# TEC_DRV.net
KiCad netlist of a schematic drawn in Altium Designer
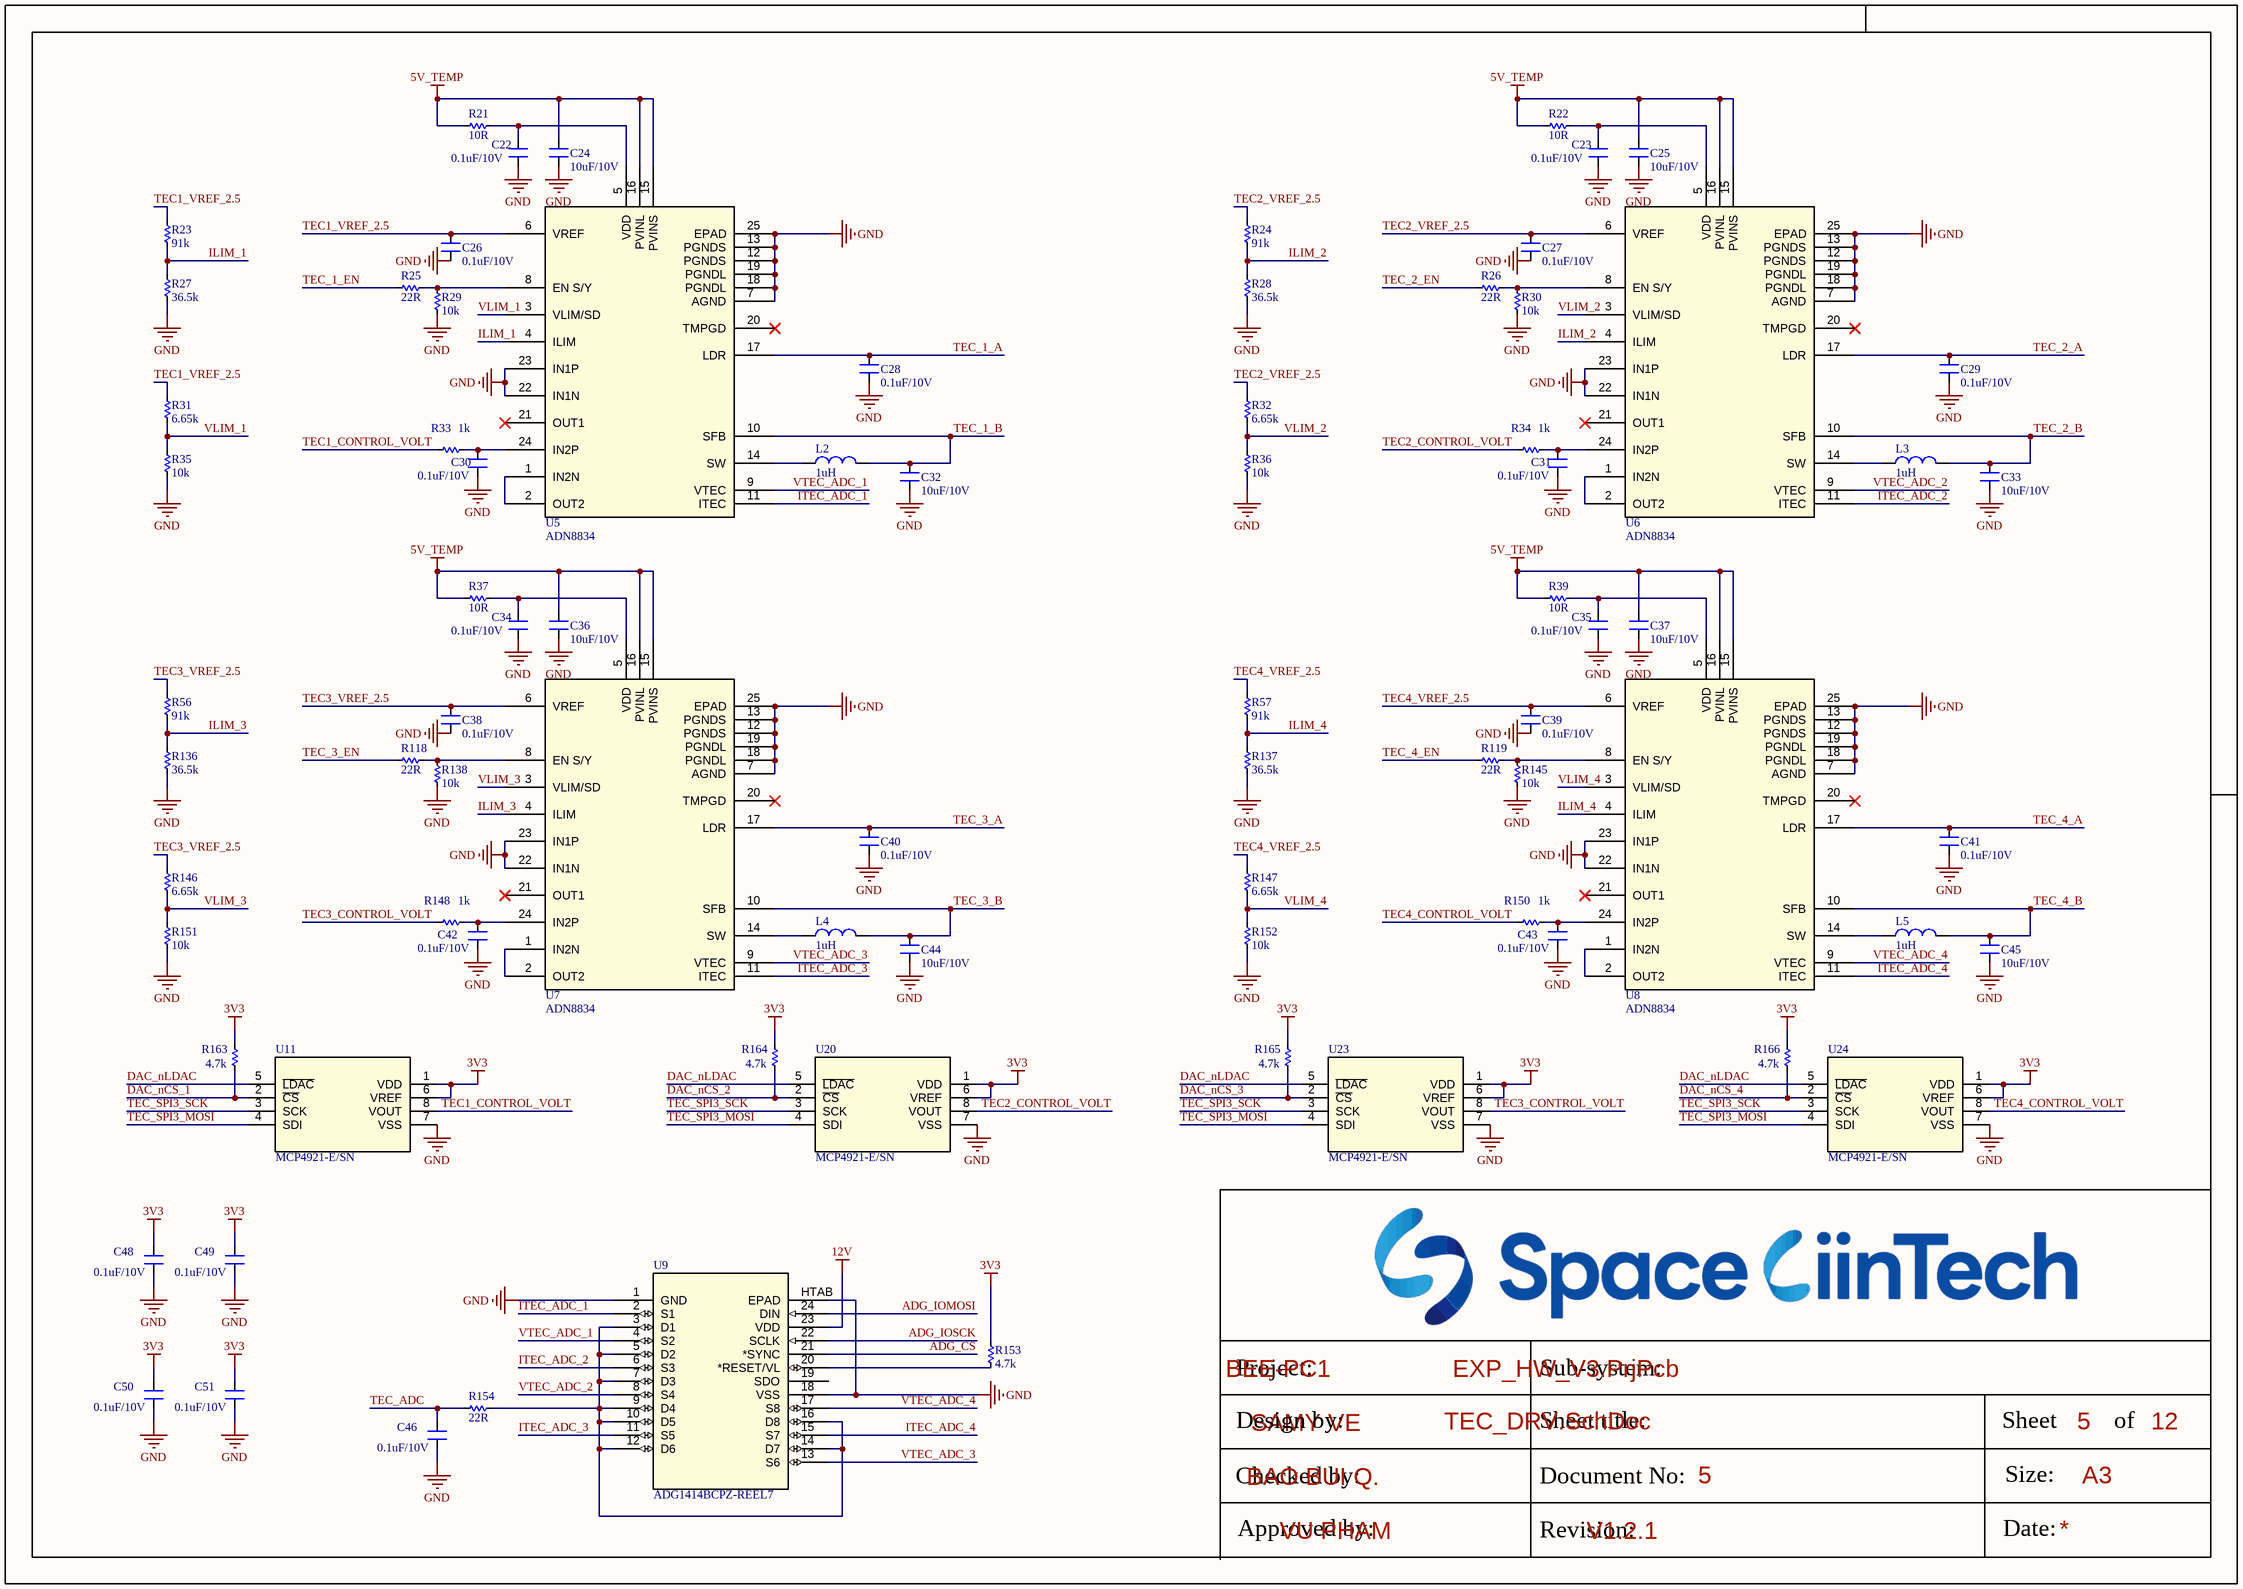
[diagram p0: TEC_DRV.SchDoc]

(export (version "E")
  (design (tool "Eeschema 10.0.6"))
  (components
    (comp (ref "C22")
      (value "0.1uF/10V")
      (footprint "CAP_C_1608X80")
      (libsource (lib "EXP_HW_V3") (part "Capacitors"))
    )
    (comp (ref "C23")
      (value "0.1uF/10V")
      (footprint "CAP_C_1608X80")
      (libsource (lib "EXP_HW_V3") (part "Capacitors"))
    )
    (comp (ref "C24")
      (value "10uF/10V")
      (footprint "CAP_C_1608X80")
      (libsource (lib "EXP_HW_V3") (part "Capacitors"))
    )
    (comp (ref "C25")
      (value "10uF/10V")
      (footprint "CAP_C_1608X80")
      (libsource (lib "EXP_HW_V3") (part "Capacitors"))
    )
    (comp (ref "C26")
      (value "0.1uF/10V")
      (footprint "CAP_C_1608X80")
      (libsource (lib "EXP_HW_V3") (part "Capacitors"))
    )
    (comp (ref "C27")
      (value "0.1uF/10V")
      (footprint "CAP_C_1608X80")
      (libsource (lib "EXP_HW_V3") (part "Capacitors"))
    )
    (comp (ref "C28")
      (value "0.1uF/10V")
      (footprint "CAP_C_1608X80")
      (libsource (lib "EXP_HW_V3") (part "Capacitors"))
    )
    (comp (ref "C29")
      (value "0.1uF/10V")
      (footprint "CAP_C_1608X80")
      (libsource (lib "EXP_HW_V3") (part "Capacitors"))
    )
    (comp (ref "C30")
      (value "0.1uF/10V")
      (footprint "CAP_C_1608X80")
      (libsource (lib "EXP_HW_V3") (part "Capacitors"))
    )
    (comp (ref "C31")
      (value "0.1uF/10V")
      (footprint "CAP_C_1608X80")
      (libsource (lib "EXP_HW_V3") (part "Capacitors"))
    )
    (comp (ref "C32")
      (value "10uF/10V")
      (footprint "CAP_C_1608X80")
      (libsource (lib "EXP_HW_V3") (part "Capacitors"))
    )
    (comp (ref "C33")
      (value "10uF/10V")
      (footprint "CAP_C_1608X80")
      (libsource (lib "EXP_HW_V3") (part "Capacitors"))
    )
    (comp (ref "C34")
      (value "0.1uF/10V")
      (footprint "CAP_C_1608X80")
      (libsource (lib "EXP_HW_V3") (part "Capacitors"))
    )
    (comp (ref "C35")
      (value "0.1uF/10V")
      (footprint "CAP_C_1608X80")
      (libsource (lib "EXP_HW_V3") (part "Capacitors"))
    )
    (comp (ref "C36")
      (value "10uF/10V")
      (footprint "CAP_C_1608X80")
      (libsource (lib "EXP_HW_V3") (part "Capacitors"))
    )
    (comp (ref "C37")
      (value "10uF/10V")
      (footprint "CAP_C_1608X80")
      (libsource (lib "EXP_HW_V3") (part "Capacitors"))
    )
    (comp (ref "C38")
      (value "0.1uF/10V")
      (footprint "CAP_C_1608X80")
      (libsource (lib "EXP_HW_V3") (part "Capacitors"))
    )
    (comp (ref "C39")
      (value "0.1uF/10V")
      (footprint "CAP_C_1608X80")
      (libsource (lib "EXP_HW_V3") (part "Capacitors"))
    )
    (comp (ref "C40")
      (value "0.1uF/10V")
      (footprint "CAP_C_1608X80")
      (libsource (lib "EXP_HW_V3") (part "Capacitors"))
    )
    (comp (ref "C41")
      (value "0.1uF/10V")
      (footprint "CAP_C_1608X80")
      (libsource (lib "EXP_HW_V3") (part "Capacitors"))
    )
    (comp (ref "C42")
      (value "0.1uF/10V")
      (footprint "CAP_C_1608X80")
      (libsource (lib "EXP_HW_V3") (part "Capacitors"))
    )
    (comp (ref "C43")
      (value "0.1uF/10V")
      (footprint "CAP_C_1608X80")
      (libsource (lib "EXP_HW_V3") (part "Capacitors"))
    )
    (comp (ref "C44")
      (value "10uF/10V")
      (footprint "CAP_C_1608X80")
      (libsource (lib "EXP_HW_V3") (part "Capacitors"))
    )
    (comp (ref "C45")
      (value "10uF/10V")
      (footprint "CAP_C_1608X80")
      (libsource (lib "EXP_HW_V3") (part "Capacitors"))
    )
    (comp (ref "C46")
      (value "0.1uF/10V")
      (footprint "CAP_C_1608X80")
      (libsource (lib "EXP_HW_V3") (part "Capacitors"))
    )
    (comp (ref "C48")
      (value "0.1uF/10V")
      (footprint "CAP_C_1608X80")
      (libsource (lib "EXP_HW_V3") (part "Capacitors"))
    )
    (comp (ref "C49")
      (value "0.1uF/10V")
      (footprint "CAP_C_1608X80")
      (libsource (lib "EXP_HW_V3") (part "Capacitors"))
    )
    (comp (ref "C50")
      (value "0.1uF/10V")
      (footprint "CAP_C_1608X80")
      (libsource (lib "EXP_HW_V3") (part "Capacitors"))
    )
    (comp (ref "C51")
      (value "0.1uF/10V")
      (footprint "CAP_C_1608X80")
      (libsource (lib "EXP_HW_V3") (part "Capacitors"))
    )
    (comp (ref "L2")
      (value "1uH")
      (footprint "L-SMD-M-3.5x3.5x2mm")
      (fields
        (field (name "PARTNO") "78477010")
        (field (name "MANUFACTURER") "Wurth Elektronik")
        (field (name "CREATED BY") "Baojun Chen")
      )
      (libsource (lib "EXP_HW_V3") (part "L-SMD-1"))
    )
    (comp (ref "L3")
      (value "1uH")
      (footprint "L-SMD-M-3.5x3.5x2mm")
      (fields
        (field (name "PARTNO") "78477010")
        (field (name "MANUFACTURER") "Wurth Elektronik")
        (field (name "CREATED BY") "Baojun Chen")
      )
      (libsource (lib "EXP_HW_V3") (part "L-SMD-1"))
    )
    (comp (ref "L4")
      (value "1uH")
      (footprint "L-SMD-M-3.5x3.5x2mm")
      (fields
        (field (name "PARTNO") "78477010")
        (field (name "MANUFACTURER") "Wurth Elektronik")
        (field (name "CREATED BY") "Baojun Chen")
      )
      (libsource (lib "EXP_HW_V3") (part "L-SMD-1"))
    )
    (comp (ref "L5")
      (value "1uH")
      (footprint "L-SMD-M-3.5x3.5x2mm")
      (fields
        (field (name "PARTNO") "78477010")
        (field (name "MANUFACTURER") "Wurth Elektronik")
        (field (name "CREATED BY") "Baojun Chen")
      )
      (libsource (lib "EXP_HW_V3") (part "L-SMD-1"))
    )
    (comp (ref "R21")
      (value "10R")
      (footprint "RES_C_1608X60")
      (description "SMD")
      (fields
        (field (name "MANUFACTURER") "Generic Components")
        (field (name "PUBLISHER") "Altium Hobart Technology Centre")
      )
      (libsource (lib "EXP_HW_V3") (part "Res SMD"))
    )
    (comp (ref "R22")
      (value "10R")
      (footprint "RES_C_1608X60")
      (description "SMD")
      (fields
        (field (name "MANUFACTURER") "Generic Components")
        (field (name "PUBLISHER") "Altium Hobart Technology Centre")
      )
      (libsource (lib "EXP_HW_V3") (part "Res SMD"))
    )
    (comp (ref "R23")
      (value "91k")
      (footprint "RES_C_1608X60")
      (description "SMD")
      (fields
        (field (name "MANUFACTURER") "Generic Components")
        (field (name "PUBLISHER") "Altium Hobart Technology Centre")
      )
      (libsource (lib "EXP_HW_V3") (part "Res SMD"))
    )
    (comp (ref "R24")
      (value "91k")
      (footprint "RES_C_1608X60")
      (description "SMD")
      (fields
        (field (name "MANUFACTURER") "Generic Components")
        (field (name "PUBLISHER") "Altium Hobart Technology Centre")
      )
      (libsource (lib "EXP_HW_V3") (part "Res SMD"))
    )
    (comp (ref "R25")
      (value "22R")
      (footprint "RES_C_1608X60")
      (description "SMD")
      (fields
        (field (name "MANUFACTURER") "Generic Components")
        (field (name "PUBLISHER") "Altium Hobart Technology Centre")
      )
      (libsource (lib "EXP_HW_V3") (part "Res SMD"))
    )
    (comp (ref "R26")
      (value "22R")
      (footprint "RES_C_1608X60")
      (description "SMD")
      (fields
        (field (name "MANUFACTURER") "Generic Components")
        (field (name "PUBLISHER") "Altium Hobart Technology Centre")
      )
      (libsource (lib "EXP_HW_V3") (part "Res SMD"))
    )
    (comp (ref "R27")
      (value "36.5k")
      (footprint "RES_C_1608X60")
      (description "SMD")
      (fields
        (field (name "MANUFACTURER") "Generic Components")
        (field (name "PUBLISHER") "Altium Hobart Technology Centre")
      )
      (libsource (lib "EXP_HW_V3") (part "Res SMD"))
    )
    (comp (ref "R28")
      (value "36.5k")
      (footprint "RES_C_1608X60")
      (description "SMD")
      (fields
        (field (name "MANUFACTURER") "Generic Components")
        (field (name "PUBLISHER") "Altium Hobart Technology Centre")
      )
      (libsource (lib "EXP_HW_V3") (part "Res SMD"))
    )
    (comp (ref "R29")
      (value "10k")
      (footprint "RES_C_1608X60")
      (description "SMD")
      (fields
        (field (name "MANUFACTURER") "Generic Components")
        (field (name "PUBLISHER") "Altium Hobart Technology Centre")
      )
      (libsource (lib "EXP_HW_V3") (part "Res SMD"))
    )
    (comp (ref "R30")
      (value "10k")
      (footprint "RES_C_1608X60")
      (description "SMD")
      (fields
        (field (name "MANUFACTURER") "Generic Components")
        (field (name "PUBLISHER") "Altium Hobart Technology Centre")
      )
      (libsource (lib "EXP_HW_V3") (part "Res SMD"))
    )
    (comp (ref "R31")
      (value "6.65k")
      (footprint "RES_C_1608X60")
      (description "SMD")
      (fields
        (field (name "MANUFACTURER") "Generic Components")
        (field (name "PUBLISHER") "Altium Hobart Technology Centre")
      )
      (libsource (lib "EXP_HW_V3") (part "Res SMD"))
    )
    (comp (ref "R32")
      (value "6.65k")
      (footprint "RES_C_1608X60")
      (description "SMD")
      (fields
        (field (name "MANUFACTURER") "Generic Components")
        (field (name "PUBLISHER") "Altium Hobart Technology Centre")
      )
      (libsource (lib "EXP_HW_V3") (part "Res SMD"))
    )
    (comp (ref "R33")
      (value "1k")
      (footprint "RES_C_1608X60")
      (description "SMD")
      (fields
        (field (name "MANUFACTURER") "Generic Components")
        (field (name "PUBLISHER") "Altium Hobart Technology Centre")
      )
      (libsource (lib "EXP_HW_V3") (part "Res SMD"))
    )
    (comp (ref "R34")
      (value "1k")
      (footprint "RES_C_1608X60")
      (description "SMD")
      (fields
        (field (name "MANUFACTURER") "Generic Components")
        (field (name "PUBLISHER") "Altium Hobart Technology Centre")
      )
      (libsource (lib "EXP_HW_V3") (part "Res SMD"))
    )
    (comp (ref "R35")
      (value "10k")
      (footprint "RES_C_1608X60")
      (description "SMD")
      (fields
        (field (name "MANUFACTURER") "Generic Components")
        (field (name "PUBLISHER") "Altium Hobart Technology Centre")
      )
      (libsource (lib "EXP_HW_V3") (part "Res SMD"))
    )
    (comp (ref "R36")
      (value "10k")
      (footprint "RES_C_1608X60")
      (description "SMD")
      (fields
        (field (name "MANUFACTURER") "Generic Components")
        (field (name "PUBLISHER") "Altium Hobart Technology Centre")
      )
      (libsource (lib "EXP_HW_V3") (part "Res SMD"))
    )
    (comp (ref "R37")
      (value "10R")
      (footprint "RES_C_1608X60")
      (description "SMD")
      (fields
        (field (name "MANUFACTURER") "Generic Components")
        (field (name "PUBLISHER") "Altium Hobart Technology Centre")
      )
      (libsource (lib "EXP_HW_V3") (part "Res SMD"))
    )
    (comp (ref "R39")
      (value "10R")
      (footprint "RES_C_1608X60")
      (description "SMD")
      (fields
        (field (name "MANUFACTURER") "Generic Components")
        (field (name "PUBLISHER") "Altium Hobart Technology Centre")
      )
      (libsource (lib "EXP_HW_V3") (part "Res SMD"))
    )
    (comp (ref "R56")
      (value "91k")
      (footprint "RES_C_1608X60")
      (description "SMD")
      (fields
        (field (name "MANUFACTURER") "Generic Components")
        (field (name "PUBLISHER") "Altium Hobart Technology Centre")
      )
      (libsource (lib "EXP_HW_V3") (part "Res SMD"))
    )
    (comp (ref "R57")
      (value "91k")
      (footprint "RES_C_1608X60")
      (description "SMD")
      (fields
        (field (name "MANUFACTURER") "Generic Components")
        (field (name "PUBLISHER") "Altium Hobart Technology Centre")
      )
      (libsource (lib "EXP_HW_V3") (part "Res SMD"))
    )
    (comp (ref "R118")
      (value "22R")
      (footprint "RES_C_1608X60")
      (description "SMD")
      (fields
        (field (name "MANUFACTURER") "Generic Components")
        (field (name "PUBLISHER") "Altium Hobart Technology Centre")
      )
      (libsource (lib "EXP_HW_V3") (part "Res SMD"))
    )
    (comp (ref "R119")
      (value "22R")
      (footprint "RES_C_1608X60")
      (description "SMD")
      (fields
        (field (name "MANUFACTURER") "Generic Components")
        (field (name "PUBLISHER") "Altium Hobart Technology Centre")
      )
      (libsource (lib "EXP_HW_V3") (part "Res SMD"))
    )
    (comp (ref "R136")
      (value "36.5k")
      (footprint "RES_C_1608X60")
      (description "SMD")
      (fields
        (field (name "MANUFACTURER") "Generic Components")
        (field (name "PUBLISHER") "Altium Hobart Technology Centre")
      )
      (libsource (lib "EXP_HW_V3") (part "Res SMD"))
    )
    (comp (ref "R137")
      (value "36.5k")
      (footprint "RES_C_1608X60")
      (description "SMD")
      (fields
        (field (name "MANUFACTURER") "Generic Components")
        (field (name "PUBLISHER") "Altium Hobart Technology Centre")
      )
      (libsource (lib "EXP_HW_V3") (part "Res SMD"))
    )
    (comp (ref "R138")
      (value "10k")
      (footprint "RES_C_1608X60")
      (description "SMD")
      (fields
        (field (name "MANUFACTURER") "Generic Components")
        (field (name "PUBLISHER") "Altium Hobart Technology Centre")
      )
      (libsource (lib "EXP_HW_V3") (part "Res SMD"))
    )
    (comp (ref "R145")
      (value "10k")
      (footprint "RES_C_1608X60")
      (description "SMD")
      (fields
        (field (name "MANUFACTURER") "Generic Components")
        (field (name "PUBLISHER") "Altium Hobart Technology Centre")
      )
      (libsource (lib "EXP_HW_V3") (part "Res SMD"))
    )
    (comp (ref "R146")
      (value "6.65k")
      (footprint "RES_C_1608X60")
      (description "SMD")
      (fields
        (field (name "MANUFACTURER") "Generic Components")
        (field (name "PUBLISHER") "Altium Hobart Technology Centre")
      )
      (libsource (lib "EXP_HW_V3") (part "Res SMD"))
    )
    (comp (ref "R147")
      (value "6.65k")
      (footprint "RES_C_1608X60")
      (description "SMD")
      (fields
        (field (name "MANUFACTURER") "Generic Components")
        (field (name "PUBLISHER") "Altium Hobart Technology Centre")
      )
      (libsource (lib "EXP_HW_V3") (part "Res SMD"))
    )
    (comp (ref "R148")
      (value "1k")
      (footprint "RES_C_1608X60")
      (description "SMD")
      (fields
        (field (name "MANUFACTURER") "Generic Components")
        (field (name "PUBLISHER") "Altium Hobart Technology Centre")
      )
      (libsource (lib "EXP_HW_V3") (part "Res SMD"))
    )
    (comp (ref "R150")
      (value "1k")
      (footprint "RES_C_1608X60")
      (description "SMD")
      (fields
        (field (name "MANUFACTURER") "Generic Components")
        (field (name "PUBLISHER") "Altium Hobart Technology Centre")
      )
      (libsource (lib "EXP_HW_V3") (part "Res SMD"))
    )
    (comp (ref "R151")
      (value "10k")
      (footprint "RES_C_1608X60")
      (description "SMD")
      (fields
        (field (name "MANUFACTURER") "Generic Components")
        (field (name "PUBLISHER") "Altium Hobart Technology Centre")
      )
      (libsource (lib "EXP_HW_V3") (part "Res SMD"))
    )
    (comp (ref "R152")
      (value "10k")
      (footprint "RES_C_1608X60")
      (description "SMD")
      (fields
        (field (name "MANUFACTURER") "Generic Components")
        (field (name "PUBLISHER") "Altium Hobart Technology Centre")
      )
      (libsource (lib "EXP_HW_V3") (part "Res SMD"))
    )
    (comp (ref "R153")
      (value "4.7k")
      (footprint "RES_C_1608X60")
      (description "SMD")
      (fields
        (field (name "MANUFACTURER") "Generic Components")
        (field (name "PUBLISHER") "Altium Hobart Technology Centre")
      )
      (libsource (lib "EXP_HW_V3") (part "Res SMD"))
    )
    (comp (ref "R154")
      (value "22R")
      (footprint "RES_C_1608X60")
      (description "SMD")
      (fields
        (field (name "MANUFACTURER") "Generic Components")
        (field (name "PUBLISHER") "Altium Hobart Technology Centre")
      )
      (libsource (lib "EXP_HW_V3") (part "Res SMD"))
    )
    (comp (ref "R163")
      (value "4.7k")
      (footprint "RES_C_1608X60")
      (description "SMD")
      (fields
        (field (name "MANUFACTURER") "Generic Components")
        (field (name "PUBLISHER") "Altium Hobart Technology Centre")
      )
      (libsource (lib "EXP_HW_V3") (part "Res SMD"))
    )
    (comp (ref "R164")
      (value "4.7k")
      (footprint "RES_C_1608X60")
      (description "SMD")
      (fields
        (field (name "MANUFACTURER") "Generic Components")
        (field (name "PUBLISHER") "Altium Hobart Technology Centre")
      )
      (libsource (lib "EXP_HW_V3") (part "Res SMD"))
    )
    (comp (ref "R165")
      (value "4.7k")
      (footprint "RES_C_1608X60")
      (description "SMD")
      (fields
        (field (name "MANUFACTURER") "Generic Components")
        (field (name "PUBLISHER") "Altium Hobart Technology Centre")
      )
      (libsource (lib "EXP_HW_V3") (part "Res SMD"))
    )
    (comp (ref "R166")
      (value "4.7k")
      (footprint "RES_C_1608X60")
      (description "SMD")
      (fields
        (field (name "MANUFACTURER") "Generic Components")
        (field (name "PUBLISHER") "Altium Hobart Technology Centre")
      )
      (libsource (lib "EXP_HW_V3") (part "Res SMD"))
    )
    (comp (ref "U5")
      (value "ADN8834")
      (footprint "ADN8834")
      (description "IC THERMO COOLER DRIVER 24LFCSP")
      (libsource (lib "EXP_HW_V3") (part "ADN8834"))
    )
    (comp (ref "U6")
      (value "ADN8834")
      (footprint "ADN8834")
      (description "IC THERMO COOLER DRIVER 24LFCSP")
      (libsource (lib "EXP_HW_V3") (part "ADN8834"))
    )
    (comp (ref "U7")
      (value "ADN8834")
      (footprint "ADN8834")
      (description "IC THERMO COOLER DRIVER 24LFCSP")
      (libsource (lib "EXP_HW_V3") (part "ADN8834"))
    )
    (comp (ref "U8")
      (value "ADN8834")
      (footprint "ADN8834")
      (description "IC THERMO COOLER DRIVER 24LFCSP")
      (libsource (lib "EXP_HW_V3") (part "ADN8834"))
    )
    (comp (ref "U9")
      (value "ADG1414BCPZ-REEL7")
      (footprint "ADG1414BCPZ-REEL7")
      (description "IC SW SPST-NOX8 11.5OHM 24LFCSP")
      (libsource (lib "EXP_HW_V3") (part "ADG1414"))
    )
    (comp (ref "U11")
      (value "MCP4921-E/SN")
      (footprint "SO8")
      (description "12 Bit Digital to Analog Converter, P/N: MCP4921-E/SN")
      (libsource (lib "EXP_HW_V3") (part "MCP4921-E/SN"))
    )
    (comp (ref "U20")
      (value "MCP4921-E/SN")
      (footprint "SO8")
      (description "12 Bit Digital to Analog Converter, P/N: MCP4921-E/SN")
      (libsource (lib "EXP_HW_V3") (part "MCP4921-E/SN"))
    )
    (comp (ref "U23")
      (value "MCP4921-E/SN")
      (footprint "SO8")
      (description "12 Bit Digital to Analog Converter, P/N: MCP4921-E/SN")
      (libsource (lib "EXP_HW_V3") (part "MCP4921-E/SN"))
    )
    (comp (ref "U24")
      (value "MCP4921-E/SN")
      (footprint "SO8")
      (description "12 Bit Digital to Analog Converter, P/N: MCP4921-E/SN")
      (libsource (lib "EXP_HW_V3") (part "MCP4921-E/SN"))
    )
  )
  (nets
    (net (code "1") (name "/ADG_CS") (class "Default")
      (node (ref "U9") (pin "21") (pinfunction "*SYNC_21") (pintype "passive"))
    )
    (net (code "2") (name "/ADG_IOMOSI") (class "Default")
      (node (ref "U9") (pin "24") (pinfunction "DIN_24") (pintype "input"))
    )
    (net (code "3") (name "/ADG_IOSCK") (class "Default")
      (node (ref "U9") (pin "22") (pinfunction "SCLK_22") (pintype "input"))
    )
    (net (code "4") (name "/DAC_nCS_1") (class "Default")
      (node (ref "R163") (pin "2") (pinfunction "2_2") (pintype "passive"))
      (node (ref "U11") (pin "2") (pinfunction "~{CS}_2") (pintype "passive"))
    )
    (net (code "5") (name "/DAC_nCS_2") (class "Default")
      (node (ref "R164") (pin "2") (pinfunction "2_2") (pintype "passive"))
      (node (ref "U20") (pin "2") (pinfunction "~{CS}_2") (pintype "passive"))
    )
    (net (code "6") (name "/DAC_nCS_3") (class "Default")
      (node (ref "R165") (pin "2") (pinfunction "2_2") (pintype "passive"))
      (node (ref "U23") (pin "2") (pinfunction "~{CS}_2") (pintype "passive"))
    )
    (net (code "7") (name "/DAC_nCS_4") (class "Default")
      (node (ref "R166") (pin "2") (pinfunction "2_2") (pintype "passive"))
      (node (ref "U24") (pin "2") (pinfunction "~{CS}_2") (pintype "passive"))
    )
    (net (code "8") (name "/DAC_nLDAC") (class "Default")
      (node (ref "U11") (pin "5") (pinfunction "~{LDAC}_5") (pintype "passive"))
      (node (ref "U20") (pin "5") (pinfunction "~{LDAC}_5") (pintype "passive"))
      (node (ref "U23") (pin "5") (pinfunction "~{LDAC}_5") (pintype "passive"))
      (node (ref "U24") (pin "5") (pinfunction "~{LDAC}_5") (pintype "passive"))
    )
    (net (code "9") (name "/ILIM_1") (class "Default")
      (node (ref "R23") (pin "2") (pinfunction "2_2") (pintype "passive"))
      (node (ref "R27") (pin "1") (pinfunction "1_1") (pintype "passive"))
      (node (ref "U5") (pin "4") (pinfunction "ILIM_4") (pintype "passive"))
    )
    (net (code "10") (name "/ILIM_2") (class "Default")
      (node (ref "R24") (pin "2") (pinfunction "2_2") (pintype "passive"))
      (node (ref "R28") (pin "1") (pinfunction "1_1") (pintype "passive"))
      (node (ref "U6") (pin "4") (pinfunction "ILIM_4") (pintype "passive"))
    )
    (net (code "11") (name "/ILIM_3") (class "Default")
      (node (ref "R136") (pin "1") (pinfunction "1_1") (pintype "passive"))
      (node (ref "R56") (pin "2") (pinfunction "2_2") (pintype "passive"))
      (node (ref "U7") (pin "4") (pinfunction "ILIM_4") (pintype "passive"))
    )
    (net (code "12") (name "/ILIM_4") (class "Default")
      (node (ref "R137") (pin "1") (pinfunction "1_1") (pintype "passive"))
      (node (ref "R57") (pin "2") (pinfunction "2_2") (pintype "passive"))
      (node (ref "U8") (pin "4") (pinfunction "ILIM_4") (pintype "passive"))
    )
    (net (code "13") (name "/ITEC_ADC_1") (class "Default")
      (node (ref "U5") (pin "11") (pinfunction "ITEC_11") (pintype "passive"))
      (node (ref "U9") (pin "2") (pinfunction "S1_2") (pintype "bidirectional"))
    )
    (net (code "14") (name "/ITEC_ADC_2") (class "Default")
      (node (ref "U6") (pin "11") (pinfunction "ITEC_11") (pintype "passive"))
      (node (ref "U9") (pin "6") (pinfunction "S3_6") (pintype "bidirectional"))
    )
    (net (code "15") (name "/ITEC_ADC_3") (class "Default")
      (node (ref "U7") (pin "11") (pinfunction "ITEC_11") (pintype "passive"))
      (node (ref "U9") (pin "11") (pinfunction "S5_11") (pintype "bidirectional"))
    )
    (net (code "16") (name "/ITEC_ADC_4") (class "Default")
      (node (ref "U8") (pin "11") (pinfunction "ITEC_11") (pintype "passive"))
      (node (ref "U9") (pin "15") (pinfunction "S7_15") (pintype "bidirectional"))
    )
    (net (code "17") (name "/TEC1_CONTROL_VOLT") (class "Default")
      (node (ref "R33") (pin "1") (pinfunction "1_1") (pintype "passive"))
      (node (ref "U11") (pin "8") (pinfunction "VOUT_8") (pintype "passive"))
    )
    (net (code "18") (name "/TEC1_VREF_2.5") (class "Default")
      (node (ref "C26") (pin "2") (pinfunction "2_2") (pintype "passive"))
      (node (ref "R23") (pin "1") (pinfunction "1_1") (pintype "passive"))
      (node (ref "R31") (pin "1") (pinfunction "1_1") (pintype "passive"))
      (node (ref "U5") (pin "6") (pinfunction "VREF_6") (pintype "passive"))
    )
    (net (code "19") (name "/TEC2_CONTROL_VOLT") (class "Default")
      (node (ref "R34") (pin "1") (pinfunction "1_1") (pintype "passive"))
      (node (ref "U20") (pin "8") (pinfunction "VOUT_8") (pintype "passive"))
    )
    (net (code "20") (name "/TEC2_VREF_2.5") (class "Default")
      (node (ref "C27") (pin "2") (pinfunction "2_2") (pintype "passive"))
      (node (ref "R24") (pin "1") (pinfunction "1_1") (pintype "passive"))
      (node (ref "R32") (pin "1") (pinfunction "1_1") (pintype "passive"))
      (node (ref "U6") (pin "6") (pinfunction "VREF_6") (pintype "passive"))
    )
    (net (code "21") (name "/TEC3_CONTROL_VOLT") (class "Default")
      (node (ref "R148") (pin "1") (pinfunction "1_1") (pintype "passive"))
      (node (ref "U23") (pin "8") (pinfunction "VOUT_8") (pintype "passive"))
    )
    (net (code "22") (name "/TEC3_VREF_2.5") (class "Default")
      (node (ref "C38") (pin "2") (pinfunction "2_2") (pintype "passive"))
      (node (ref "R146") (pin "1") (pinfunction "1_1") (pintype "passive"))
      (node (ref "R56") (pin "1") (pinfunction "1_1") (pintype "passive"))
      (node (ref "U7") (pin "6") (pinfunction "VREF_6") (pintype "passive"))
    )
    (net (code "23") (name "/TEC4_CONTROL_VOLT") (class "Default")
      (node (ref "R150") (pin "1") (pinfunction "1_1") (pintype "passive"))
      (node (ref "U24") (pin "8") (pinfunction "VOUT_8") (pintype "passive"))
    )
    (net (code "24") (name "/TEC4_VREF_2.5") (class "Default")
      (node (ref "C39") (pin "2") (pinfunction "2_2") (pintype "passive"))
      (node (ref "R147") (pin "1") (pinfunction "1_1") (pintype "passive"))
      (node (ref "R57") (pin "1") (pinfunction "1_1") (pintype "passive"))
      (node (ref "U8") (pin "6") (pinfunction "VREF_6") (pintype "passive"))
    )
    (net (code "25") (name "/TEC_1_A") (class "Default")
      (node (ref "C28") (pin "2") (pinfunction "2_2") (pintype "passive"))
      (node (ref "U5") (pin "17") (pinfunction "LDR_17") (pintype "passive"))
    )
    (net (code "26") (name "/TEC_1_B") (class "Default")
      (node (ref "C32") (pin "2") (pinfunction "2_2") (pintype "passive"))
      (node (ref "L2") (pin "2") (pinfunction "2_2") (pintype "passive"))
      (node (ref "U5") (pin "10") (pinfunction "SFB_10") (pintype "passive"))
    )
    (net (code "27") (name "/TEC_1_EN") (class "Default")
      (node (ref "R25") (pin "1") (pinfunction "1_1") (pintype "passive"))
    )
    (net (code "28") (name "/TEC_2_A") (class "Default")
      (node (ref "C29") (pin "2") (pinfunction "2_2") (pintype "passive"))
      (node (ref "U6") (pin "17") (pinfunction "LDR_17") (pintype "passive"))
    )
    (net (code "29") (name "/TEC_2_B") (class "Default")
      (node (ref "C33") (pin "2") (pinfunction "2_2") (pintype "passive"))
      (node (ref "L3") (pin "2") (pinfunction "2_2") (pintype "passive"))
      (node (ref "U6") (pin "10") (pinfunction "SFB_10") (pintype "passive"))
    )
    (net (code "30") (name "/TEC_2_EN") (class "Default")
      (node (ref "R26") (pin "1") (pinfunction "1_1") (pintype "passive"))
    )
    (net (code "31") (name "/TEC_3_A") (class "Default")
      (node (ref "C40") (pin "2") (pinfunction "2_2") (pintype "passive"))
      (node (ref "U7") (pin "17") (pinfunction "LDR_17") (pintype "passive"))
    )
    (net (code "32") (name "/TEC_3_B") (class "Default")
      (node (ref "C44") (pin "2") (pinfunction "2_2") (pintype "passive"))
      (node (ref "L4") (pin "2") (pinfunction "2_2") (pintype "passive"))
      (node (ref "U7") (pin "10") (pinfunction "SFB_10") (pintype "passive"))
    )
    (net (code "33") (name "/TEC_3_EN") (class "Default")
      (node (ref "R118") (pin "1") (pinfunction "1_1") (pintype "passive"))
    )
    (net (code "34") (name "/TEC_4_A") (class "Default")
      (node (ref "C41") (pin "2") (pinfunction "2_2") (pintype "passive"))
      (node (ref "U8") (pin "17") (pinfunction "LDR_17") (pintype "passive"))
    )
    (net (code "35") (name "/TEC_4_B") (class "Default")
      (node (ref "C45") (pin "2") (pinfunction "2_2") (pintype "passive"))
      (node (ref "L5") (pin "2") (pinfunction "2_2") (pintype "passive"))
      (node (ref "U8") (pin "10") (pinfunction "SFB_10") (pintype "passive"))
    )
    (net (code "36") (name "/TEC_4_EN") (class "Default")
      (node (ref "R119") (pin "1") (pinfunction "1_1") (pintype "passive"))
    )
    (net (code "37") (name "/TEC_ADC") (class "Default")
      (node (ref "C46") (pin "2") (pinfunction "2_2") (pintype "passive"))
      (node (ref "R154") (pin "1") (pinfunction "1_1") (pintype "passive"))
    )
    (net (code "38") (name "/TEC_SPI3_MOSI") (class "Default")
      (node (ref "U11") (pin "4") (pinfunction "SDI_4") (pintype "passive"))
      (node (ref "U20") (pin "4") (pinfunction "SDI_4") (pintype "passive"))
      (node (ref "U23") (pin "4") (pinfunction "SDI_4") (pintype "passive"))
      (node (ref "U24") (pin "4") (pinfunction "SDI_4") (pintype "passive"))
    )
    (net (code "39") (name "/TEC_SPI3_SCK") (class "Default")
      (node (ref "U11") (pin "3") (pinfunction "SCK_3") (pintype "passive"))
      (node (ref "U20") (pin "3") (pinfunction "SCK_3") (pintype "passive"))
      (node (ref "U23") (pin "3") (pinfunction "SCK_3") (pintype "passive"))
      (node (ref "U24") (pin "3") (pinfunction "SCK_3") (pintype "passive"))
    )
    (net (code "40") (name "/VLIM_1") (class "Default")
      (node (ref "R31") (pin "2") (pinfunction "2_2") (pintype "passive"))
      (node (ref "R35") (pin "1") (pinfunction "1_1") (pintype "passive"))
      (node (ref "U5") (pin "3") (pinfunction "VLIM/SD_3") (pintype "passive"))
    )
    (net (code "41") (name "/VLIM_2") (class "Default")
      (node (ref "R32") (pin "2") (pinfunction "2_2") (pintype "passive"))
      (node (ref "R36") (pin "1") (pinfunction "1_1") (pintype "passive"))
      (node (ref "U6") (pin "3") (pinfunction "VLIM/SD_3") (pintype "passive"))
    )
    (net (code "42") (name "/VLIM_3") (class "Default")
      (node (ref "R146") (pin "2") (pinfunction "2_2") (pintype "passive"))
      (node (ref "R151") (pin "1") (pinfunction "1_1") (pintype "passive"))
      (node (ref "U7") (pin "3") (pinfunction "VLIM/SD_3") (pintype "passive"))
    )
    (net (code "43") (name "/VLIM_4") (class "Default")
      (node (ref "R147") (pin "2") (pinfunction "2_2") (pintype "passive"))
      (node (ref "R152") (pin "1") (pinfunction "1_1") (pintype "passive"))
      (node (ref "U8") (pin "3") (pinfunction "VLIM/SD_3") (pintype "passive"))
    )
    (net (code "44") (name "/VTEC_ADC_1") (class "Default")
      (node (ref "U5") (pin "9") (pinfunction "VTEC_9") (pintype "passive"))
      (node (ref "U9") (pin "4") (pinfunction "S2_4") (pintype "bidirectional"))
    )
    (net (code "45") (name "/VTEC_ADC_2") (class "Default")
      (node (ref "U6") (pin "9") (pinfunction "VTEC_9") (pintype "passive"))
      (node (ref "U9") (pin "8") (pinfunction "S4_8") (pintype "bidirectional"))
    )
    (net (code "46") (name "/VTEC_ADC_3") (class "Default")
      (node (ref "U7") (pin "9") (pinfunction "VTEC_9") (pintype "passive"))
      (node (ref "U9") (pin "13") (pinfunction "S6_13") (pintype "bidirectional"))
    )
    (net (code "47") (name "/VTEC_ADC_4") (class "Default")
      (node (ref "U8") (pin "9") (pinfunction "VTEC_9") (pintype "passive"))
      (node (ref "U9") (pin "17") (pinfunction "S8_17") (pintype "bidirectional"))
    )
    (net (code "48") (name "3V3") (class "Default")
      (node (ref "C48") (pin "2") (pinfunction "2_2") (pintype "passive"))
      (node (ref "C49") (pin "2") (pinfunction "2_2") (pintype "passive"))
      (node (ref "C50") (pin "2") (pinfunction "2_2") (pintype "passive"))
      (node (ref "C51") (pin "2") (pinfunction "2_2") (pintype "passive"))
      (node (ref "R153") (pin "2") (pinfunction "2_2") (pintype "passive"))
      (node (ref "R163") (pin "1") (pinfunction "1_1") (pintype "passive"))
      (node (ref "R164") (pin "1") (pinfunction "1_1") (pintype "passive"))
      (node (ref "R165") (pin "1") (pinfunction "1_1") (pintype "passive"))
      (node (ref "R166") (pin "1") (pinfunction "1_1") (pintype "passive"))
      (node (ref "U11") (pin "1") (pinfunction "VDD_1") (pintype "passive"))
      (node (ref "U11") (pin "6") (pinfunction "VREF_6") (pintype "passive"))
      (node (ref "U20") (pin "1") (pinfunction "VDD_1") (pintype "passive"))
      (node (ref "U20") (pin "6") (pinfunction "VREF_6") (pintype "passive"))
      (node (ref "U23") (pin "1") (pinfunction "VDD_1") (pintype "passive"))
      (node (ref "U23") (pin "6") (pinfunction "VREF_6") (pintype "passive"))
      (node (ref "U24") (pin "1") (pinfunction "VDD_1") (pintype "passive"))
      (node (ref "U24") (pin "6") (pinfunction "VREF_6") (pintype "passive"))
    )
    (net (code "49") (name "5V_TEMP") (class "Default")
      (node (ref "C24") (pin "2") (pinfunction "2_2") (pintype "passive"))
      (node (ref "C25") (pin "2") (pinfunction "2_2") (pintype "passive"))
      (node (ref "C36") (pin "2") (pinfunction "2_2") (pintype "passive"))
      (node (ref "C37") (pin "2") (pinfunction "2_2") (pintype "passive"))
      (node (ref "R21") (pin "1") (pinfunction "1_1") (pintype "passive"))
      (node (ref "R22") (pin "1") (pinfunction "1_1") (pintype "passive"))
      (node (ref "R37") (pin "1") (pinfunction "1_1") (pintype "passive"))
      (node (ref "R39") (pin "1") (pinfunction "1_1") (pintype "passive"))
      (node (ref "U5") (pin "15") (pinfunction "PVINS_15") (pintype "passive"))
      (node (ref "U5") (pin "16") (pinfunction "PVINL_16") (pintype "passive"))
      (node (ref "U6") (pin "15") (pinfunction "PVINS_15") (pintype "passive"))
      (node (ref "U6") (pin "16") (pinfunction "PVINL_16") (pintype "passive"))
      (node (ref "U7") (pin "15") (pinfunction "PVINS_15") (pintype "passive"))
      (node (ref "U7") (pin "16") (pinfunction "PVINL_16") (pintype "passive"))
      (node (ref "U8") (pin "15") (pinfunction "PVINS_15") (pintype "passive"))
      (node (ref "U8") (pin "16") (pinfunction "PVINL_16") (pintype "passive"))
    )
    (net (code "50") (name "12V") (class "Default")
      (node (ref "U9") (pin "23") (pinfunction "VDD_23") (pintype "power_in"))
    )
    (net (code "51") (name "GND") (class "Default")
      (node (ref "C22") (pin "1") (pinfunction "1_1") (pintype "passive"))
      (node (ref "C23") (pin "1") (pinfunction "1_1") (pintype "passive"))
      (node (ref "C24") (pin "1") (pinfunction "1_1") (pintype "passive"))
      (node (ref "C25") (pin "1") (pinfunction "1_1") (pintype "passive"))
      (node (ref "C26") (pin "1") (pinfunction "1_1") (pintype "passive"))
      (node (ref "C27") (pin "1") (pinfunction "1_1") (pintype "passive"))
      (node (ref "C28") (pin "1") (pinfunction "1_1") (pintype "passive"))
      (node (ref "C29") (pin "1") (pinfunction "1_1") (pintype "passive"))
      (node (ref "C30") (pin "1") (pinfunction "1_1") (pintype "passive"))
      (node (ref "C31") (pin "1") (pinfunction "1_1") (pintype "passive"))
      (node (ref "C32") (pin "1") (pinfunction "1_1") (pintype "passive"))
      (node (ref "C33") (pin "1") (pinfunction "1_1") (pintype "passive"))
      (node (ref "C34") (pin "1") (pinfunction "1_1") (pintype "passive"))
      (node (ref "C35") (pin "1") (pinfunction "1_1") (pintype "passive"))
      (node (ref "C36") (pin "1") (pinfunction "1_1") (pintype "passive"))
      (node (ref "C37") (pin "1") (pinfunction "1_1") (pintype "passive"))
      (node (ref "C38") (pin "1") (pinfunction "1_1") (pintype "passive"))
      (node (ref "C39") (pin "1") (pinfunction "1_1") (pintype "passive"))
      (node (ref "C40") (pin "1") (pinfunction "1_1") (pintype "passive"))
      (node (ref "C41") (pin "1") (pinfunction "1_1") (pintype "passive"))
      (node (ref "C42") (pin "1") (pinfunction "1_1") (pintype "passive"))
      (node (ref "C43") (pin "1") (pinfunction "1_1") (pintype "passive"))
      (node (ref "C44") (pin "1") (pinfunction "1_1") (pintype "passive"))
      (node (ref "C45") (pin "1") (pinfunction "1_1") (pintype "passive"))
      (node (ref "C46") (pin "1") (pinfunction "1_1") (pintype "passive"))
      (node (ref "C48") (pin "1") (pinfunction "1_1") (pintype "passive"))
      (node (ref "C49") (pin "1") (pinfunction "1_1") (pintype "passive"))
      (node (ref "C50") (pin "1") (pinfunction "1_1") (pintype "passive"))
      (node (ref "C51") (pin "1") (pinfunction "1_1") (pintype "passive"))
      (node (ref "R136") (pin "2") (pinfunction "2_2") (pintype "passive"))
      (node (ref "R137") (pin "2") (pinfunction "2_2") (pintype "passive"))
      (node (ref "R138") (pin "2") (pinfunction "2_2") (pintype "passive"))
      (node (ref "R145") (pin "2") (pinfunction "2_2") (pintype "passive"))
      (node (ref "R151") (pin "2") (pinfunction "2_2") (pintype "passive"))
      (node (ref "R152") (pin "2") (pinfunction "2_2") (pintype "passive"))
      (node (ref "R27") (pin "2") (pinfunction "2_2") (pintype "passive"))
      (node (ref "R28") (pin "2") (pinfunction "2_2") (pintype "passive"))
      (node (ref "R29") (pin "2") (pinfunction "2_2") (pintype "passive"))
      (node (ref "R30") (pin "2") (pinfunction "2_2") (pintype "passive"))
      (node (ref "R35") (pin "2") (pinfunction "2_2") (pintype "passive"))
      (node (ref "R36") (pin "2") (pinfunction "2_2") (pintype "passive"))
      (node (ref "U11") (pin "7") (pinfunction "VSS_7") (pintype "passive"))
      (node (ref "U20") (pin "7") (pinfunction "VSS_7") (pintype "passive"))
      (node (ref "U23") (pin "7") (pinfunction "VSS_7") (pintype "passive"))
      (node (ref "U24") (pin "7") (pinfunction "VSS_7") (pintype "passive"))
      (node (ref "U5") (pin "12") (pinfunction "PGNDS_12") (pintype "passive"))
      (node (ref "U5") (pin "13") (pinfunction "PGNDS_13") (pintype "passive"))
      (node (ref "U5") (pin "18") (pinfunction "PGNDL_18") (pintype "passive"))
      (node (ref "U5") (pin "19") (pinfunction "PGNDL_19") (pintype "passive"))
      (node (ref "U5") (pin "22") (pinfunction "IN1N_22") (pintype "passive"))
      (node (ref "U5") (pin "23") (pinfunction "IN1P_23") (pintype "passive"))
      (node (ref "U5") (pin "25") (pinfunction "EPAD_25") (pintype "passive"))
      (node (ref "U5") (pin "7") (pinfunction "AGND_7") (pintype "passive"))
      (node (ref "U6") (pin "12") (pinfunction "PGNDS_12") (pintype "passive"))
      (node (ref "U6") (pin "13") (pinfunction "PGNDS_13") (pintype "passive"))
      (node (ref "U6") (pin "18") (pinfunction "PGNDL_18") (pintype "passive"))
      (node (ref "U6") (pin "19") (pinfunction "PGNDL_19") (pintype "passive"))
      (node (ref "U6") (pin "22") (pinfunction "IN1N_22") (pintype "passive"))
      (node (ref "U6") (pin "23") (pinfunction "IN1P_23") (pintype "passive"))
      (node (ref "U6") (pin "25") (pinfunction "EPAD_25") (pintype "passive"))
      (node (ref "U6") (pin "7") (pinfunction "AGND_7") (pintype "passive"))
      (node (ref "U7") (pin "12") (pinfunction "PGNDS_12") (pintype "passive"))
      (node (ref "U7") (pin "13") (pinfunction "PGNDS_13") (pintype "passive"))
      (node (ref "U7") (pin "18") (pinfunction "PGNDL_18") (pintype "passive"))
      (node (ref "U7") (pin "19") (pinfunction "PGNDL_19") (pintype "passive"))
      (node (ref "U7") (pin "22") (pinfunction "IN1N_22") (pintype "passive"))
      (node (ref "U7") (pin "23") (pinfunction "IN1P_23") (pintype "passive"))
      (node (ref "U7") (pin "25") (pinfunction "EPAD_25") (pintype "passive"))
      (node (ref "U7") (pin "7") (pinfunction "AGND_7") (pintype "passive"))
      (node (ref "U8") (pin "12") (pinfunction "PGNDS_12") (pintype "passive"))
      (node (ref "U8") (pin "13") (pinfunction "PGNDS_13") (pintype "passive"))
      (node (ref "U8") (pin "18") (pinfunction "PGNDL_18") (pintype "passive"))
      (node (ref "U8") (pin "19") (pinfunction "PGNDL_19") (pintype "passive"))
      (node (ref "U8") (pin "22") (pinfunction "IN1N_22") (pintype "passive"))
      (node (ref "U8") (pin "23") (pinfunction "IN1P_23") (pintype "passive"))
      (node (ref "U8") (pin "25") (pinfunction "EPAD_25") (pintype "passive"))
      (node (ref "U8") (pin "7") (pinfunction "AGND_7") (pintype "passive"))
      (node (ref "U9") (pin "1") (pinfunction "GND_1") (pintype "power_in"))
      (node (ref "U9") (pin "18") (pinfunction "VSS_18") (pintype "power_in"))
      (node (ref "U9") (pin "HTAB") (pinfunction "EPAD_HTAB") (pintype "passive"))
    )
    (net (code "52") (name "Net-(U5-EN_S{slash}Y)") (class "Default")
      (node (ref "R25") (pin "2") (pinfunction "2_2") (pintype "passive"))
      (node (ref "R29") (pin "1") (pinfunction "1_1") (pintype "passive"))
      (node (ref "U5") (pin "8") (pinfunction "EN_S/Y_8") (pintype "passive"))
    )
    (net (code "53") (name "Net-(U5-IN2N)") (class "Default")
      (node (ref "U5") (pin "1") (pinfunction "IN2N_1") (pintype "passive"))
      (node (ref "U5") (pin "2") (pinfunction "OUT2_2") (pintype "passive"))
    )
    (net (code "54") (name "Net-(U5-IN2P)") (class "Default")
      (node (ref "C30") (pin "2") (pinfunction "2_2") (pintype "passive"))
      (node (ref "R33") (pin "2") (pinfunction "2_2") (pintype "passive"))
      (node (ref "U5") (pin "24") (pinfunction "IN2P_24") (pintype "passive"))
    )
    (net (code "55") (name "Net-(U5-SW)") (class "Default")
      (node (ref "L2") (pin "1") (pinfunction "1_1") (pintype "passive"))
      (node (ref "U5") (pin "14") (pinfunction "SW_14") (pintype "passive"))
    )
    (net (code "56") (name "Net-(U5-VDD)") (class "Default")
      (node (ref "C22") (pin "2") (pinfunction "2_2") (pintype "passive"))
      (node (ref "R21") (pin "2") (pinfunction "2_2") (pintype "passive"))
      (node (ref "U5") (pin "5") (pinfunction "VDD_5") (pintype "passive"))
    )
    (net (code "57") (name "Net-(U6-EN_S{slash}Y)") (class "Default")
      (node (ref "R26") (pin "2") (pinfunction "2_2") (pintype "passive"))
      (node (ref "R30") (pin "1") (pinfunction "1_1") (pintype "passive"))
      (node (ref "U6") (pin "8") (pinfunction "EN_S/Y_8") (pintype "passive"))
    )
    (net (code "58") (name "Net-(U6-IN2N)") (class "Default")
      (node (ref "U6") (pin "1") (pinfunction "IN2N_1") (pintype "passive"))
      (node (ref "U6") (pin "2") (pinfunction "OUT2_2") (pintype "passive"))
    )
    (net (code "59") (name "Net-(U6-IN2P)") (class "Default")
      (node (ref "C31") (pin "2") (pinfunction "2_2") (pintype "passive"))
      (node (ref "R34") (pin "2") (pinfunction "2_2") (pintype "passive"))
      (node (ref "U6") (pin "24") (pinfunction "IN2P_24") (pintype "passive"))
    )
    (net (code "60") (name "Net-(U6-SW)") (class "Default")
      (node (ref "L3") (pin "1") (pinfunction "1_1") (pintype "passive"))
      (node (ref "U6") (pin "14") (pinfunction "SW_14") (pintype "passive"))
    )
    (net (code "61") (name "Net-(U6-VDD)") (class "Default")
      (node (ref "C23") (pin "2") (pinfunction "2_2") (pintype "passive"))
      (node (ref "R22") (pin "2") (pinfunction "2_2") (pintype "passive"))
      (node (ref "U6") (pin "5") (pinfunction "VDD_5") (pintype "passive"))
    )
    (net (code "62") (name "Net-(U7-EN_S{slash}Y)") (class "Default")
      (node (ref "R118") (pin "2") (pinfunction "2_2") (pintype "passive"))
      (node (ref "R138") (pin "1") (pinfunction "1_1") (pintype "passive"))
      (node (ref "U7") (pin "8") (pinfunction "EN_S/Y_8") (pintype "passive"))
    )
    (net (code "63") (name "Net-(U7-IN2N)") (class "Default")
      (node (ref "U7") (pin "1") (pinfunction "IN2N_1") (pintype "passive"))
      (node (ref "U7") (pin "2") (pinfunction "OUT2_2") (pintype "passive"))
    )
    (net (code "64") (name "Net-(U7-IN2P)") (class "Default")
      (node (ref "C42") (pin "2") (pinfunction "2_2") (pintype "passive"))
      (node (ref "R148") (pin "2") (pinfunction "2_2") (pintype "passive"))
      (node (ref "U7") (pin "24") (pinfunction "IN2P_24") (pintype "passive"))
    )
    (net (code "65") (name "Net-(U7-SW)") (class "Default")
      (node (ref "L4") (pin "1") (pinfunction "1_1") (pintype "passive"))
      (node (ref "U7") (pin "14") (pinfunction "SW_14") (pintype "passive"))
    )
    (net (code "66") (name "Net-(U7-VDD)") (class "Default")
      (node (ref "C34") (pin "2") (pinfunction "2_2") (pintype "passive"))
      (node (ref "R37") (pin "2") (pinfunction "2_2") (pintype "passive"))
      (node (ref "U7") (pin "5") (pinfunction "VDD_5") (pintype "passive"))
    )
    (net (code "67") (name "Net-(U8-EN_S{slash}Y)") (class "Default")
      (node (ref "R119") (pin "2") (pinfunction "2_2") (pintype "passive"))
      (node (ref "R145") (pin "1") (pinfunction "1_1") (pintype "passive"))
      (node (ref "U8") (pin "8") (pinfunction "EN_S/Y_8") (pintype "passive"))
    )
    (net (code "68") (name "Net-(U8-IN2N)") (class "Default")
      (node (ref "U8") (pin "1") (pinfunction "IN2N_1") (pintype "passive"))
      (node (ref "U8") (pin "2") (pinfunction "OUT2_2") (pintype "passive"))
    )
    (net (code "69") (name "Net-(U8-IN2P)") (class "Default")
      (node (ref "C43") (pin "2") (pinfunction "2_2") (pintype "passive"))
      (node (ref "R150") (pin "2") (pinfunction "2_2") (pintype "passive"))
      (node (ref "U8") (pin "24") (pinfunction "IN2P_24") (pintype "passive"))
    )
    (net (code "70") (name "Net-(U8-SW)") (class "Default")
      (node (ref "L5") (pin "1") (pinfunction "1_1") (pintype "passive"))
      (node (ref "U8") (pin "14") (pinfunction "SW_14") (pintype "passive"))
    )
    (net (code "71") (name "Net-(U8-VDD)") (class "Default")
      (node (ref "C35") (pin "2") (pinfunction "2_2") (pintype "passive"))
      (node (ref "R39") (pin "2") (pinfunction "2_2") (pintype "passive"))
      (node (ref "U8") (pin "5") (pinfunction "VDD_5") (pintype "passive"))
    )
    (net (code "72") (name "Net-(U9-*RESET{slash}VL)") (class "Default")
      (node (ref "R153") (pin "1") (pinfunction "1_1") (pintype "passive"))
      (node (ref "U9") (pin "20") (pinfunction "*RESET/VL_20") (pintype "bidirectional"))
    )
    (net (code "73") (name "Net-(U9-D1)") (class "Default")
      (node (ref "R154") (pin "2") (pinfunction "2_2") (pintype "passive"))
      (node (ref "U9") (pin "10") (pinfunction "D5_10") (pintype "bidirectional"))
      (node (ref "U9") (pin "12") (pinfunction "D6_12") (pintype "bidirectional"))
      (node (ref "U9") (pin "14") (pinfunction "D7_14") (pintype "bidirectional"))
      (node (ref "U9") (pin "16") (pinfunction "D8_16") (pintype "bidirectional"))
      (node (ref "U9") (pin "3") (pinfunction "D1_3") (pintype "bidirectional"))
      (node (ref "U9") (pin "5") (pinfunction "D2_5") (pintype "bidirectional"))
      (node (ref "U9") (pin "7") (pinfunction "D3_7") (pintype "bidirectional"))
      (node (ref "U9") (pin "9") (pinfunction "D4_9") (pintype "bidirectional"))
    )
    (net (code "74") (name "unconnected-(U5-OUT1-Pad21)") (class "Default")
      (node (ref "U5") (pin "21") (pinfunction "OUT1_21") (pintype "passive+no_connect"))
    )
    (net (code "75") (name "unconnected-(U5-TMPGD-Pad20)") (class "Default")
      (node (ref "U5") (pin "20") (pinfunction "TMPGD_20") (pintype "passive+no_connect"))
    )
    (net (code "76") (name "unconnected-(U6-OUT1-Pad21)") (class "Default")
      (node (ref "U6") (pin "21") (pinfunction "OUT1_21") (pintype "passive+no_connect"))
    )
    (net (code "77") (name "unconnected-(U6-TMPGD-Pad20)") (class "Default")
      (node (ref "U6") (pin "20") (pinfunction "TMPGD_20") (pintype "passive+no_connect"))
    )
    (net (code "78") (name "unconnected-(U7-OUT1-Pad21)") (class "Default")
      (node (ref "U7") (pin "21") (pinfunction "OUT1_21") (pintype "passive+no_connect"))
    )
    (net (code "79") (name "unconnected-(U7-TMPGD-Pad20)") (class "Default")
      (node (ref "U7") (pin "20") (pinfunction "TMPGD_20") (pintype "passive+no_connect"))
    )
    (net (code "80") (name "unconnected-(U8-OUT1-Pad21)") (class "Default")
      (node (ref "U8") (pin "21") (pinfunction "OUT1_21") (pintype "passive+no_connect"))
    )
    (net (code "81") (name "unconnected-(U8-TMPGD-Pad20)") (class "Default")
      (node (ref "U8") (pin "20") (pinfunction "TMPGD_20") (pintype "passive+no_connect"))
    )
    (net (code "82") (name "unconnected-(U9-SDO-Pad19)") (class "Default")
      (node (ref "U9") (pin "19") (pinfunction "SDO_19") (pintype "passive"))
    )
  )
)
